# load.net
KiCad netlist of a schematic drawn in EAGLE
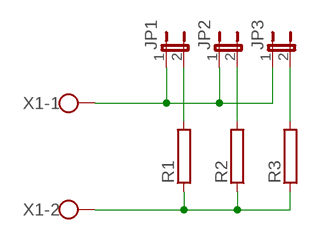
[diagram p0: schematic, sheet 1]

(export (version "E")
  (design (tool "Eeschema 10.0.6"))
  (components
    (comp (ref "JP1")
      (value "JP1E")
      (footprint "eagle-import:JP1")
      (libsource (lib "eagle-import") (part "JP1E"))
    )
    (comp (ref "JP2")
      (value "JP1E")
      (footprint "eagle-import:JP1")
      (libsource (lib "eagle-import") (part "JP1E"))
    )
    (comp (ref "JP3")
      (value "JP1E")
      (footprint "eagle-import:JP1")
      (libsource (lib "eagle-import") (part "JP1E"))
    )
    (comp (ref "R1")
      (value "RRWM8X26")
      (footprint "eagle-import:RWM8X26")
      (libsource (lib "eagle-import") (part "RRWM8X26"))
    )
    (comp (ref "R2")
      (value "RRWM8X26")
      (footprint "eagle-import:RWM8X26")
      (libsource (lib "eagle-import") (part "RRWM8X26"))
    )
    (comp (ref "R3")
      (value "RRWM8X26")
      (footprint "eagle-import:RWM8X26")
      (libsource (lib "eagle-import") (part "RRWM8X26"))
    )
    (comp (ref "X1")
      (value "W237-02P")
      (footprint "eagle-import:W237-132")
      (libsource (lib "eagle-import") (part "W237-02P"))
    )
  )
  (nets
    (net (code "1") (name "Net-(JP1-Pad2)") (class "Default")
      (node (ref "JP1") (pin "2") (pinfunction "2_2") (pintype "passive"))
      (node (ref "R1") (pin "2") (pinfunction "2_2") (pintype "passive"))
    )
    (net (code "2") (name "Net-(JP2-Pad2)") (class "Default")
      (node (ref "JP2") (pin "2") (pinfunction "2_2") (pintype "passive"))
      (node (ref "R2") (pin "2") (pinfunction "2_2") (pintype "passive"))
    )
    (net (code "3") (name "Net-(JP3-Pad2)") (class "Default")
      (node (ref "JP3") (pin "2") (pinfunction "2_2") (pintype "passive"))
      (node (ref "R3") (pin "2") (pinfunction "2_2") (pintype "passive"))
    )
    (net (code "4") (name "Net-(X1A-KL)") (class "Default")
      (node (ref "JP1") (pin "1") (pinfunction "1_1") (pintype "passive"))
      (node (ref "JP2") (pin "1") (pinfunction "1_1") (pintype "passive"))
      (node (ref "JP3") (pin "1") (pinfunction "1_1") (pintype "passive"))
      (node (ref "X1") (pin "1") (pinfunction "KL_1") (pintype "passive"))
    )
    (net (code "5") (name "Net-(X1B-KL)") (class "Default")
      (node (ref "R1") (pin "1") (pinfunction "1_1") (pintype "passive"))
      (node (ref "R2") (pin "1") (pinfunction "1_1") (pintype "passive"))
      (node (ref "R3") (pin "1") (pinfunction "1_1") (pintype "passive"))
      (node (ref "X1") (pin "2") (pinfunction "KL_2") (pintype "passive"))
    )
  )
)
